# CATS-EUROC-Baro.net
KiCad netlist of a schematic drawn in Altium Designer
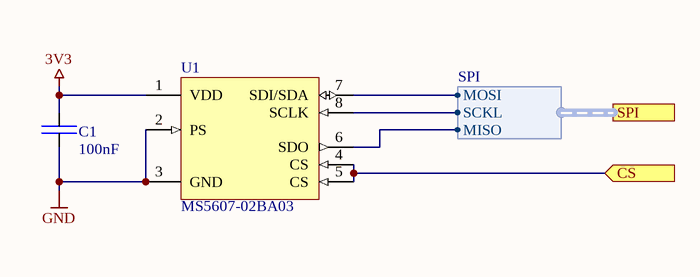
[diagram p0: CATS-EUROC-Baro.SchDoc]

(export (version "E")
  (design (tool "Eeschema 10.0.6"))
  (components
    (comp (ref "C1")
      (value "100nF")
      (footprint "SMD Keramikkondensator 0402")
      (description "SMD Ceramic Capacitor E6")
      (libsource (lib "CATS-EUROC") (part "E6 - 100nF"))
    )
    (comp (ref "U1")
      (value "MS5607-02BA03")
      (footprint "SMD IC BARO MS5607")
      (description "Barometric Pressure Sensor, with stainless\r\nsteel cap")
      (libsource (lib "Sensors") (part "MS5607-02BA03"))
    )
  )
  (nets
    (net (code "2") (name "/CS") (class "Default")
      (node (ref "U1") (pin "4") (pinfunction "CS_4") (pintype "input"))
      (node (ref "U1") (pin "5") (pinfunction "CS_5") (pintype "input"))
    )
    (net (code "3") (name "/MISO") (class "Default")
      (node (ref "U1") (pin "6") (pinfunction "SDO_6") (pintype "output"))
    )
    (net (code "4") (name "/MOSI") (class "Default")
      (node (ref "U1") (pin "7") (pinfunction "SDI/SDA_7") (pintype "bidirectional"))
    )
    (net (code "5") (name "/SCKL") (class "Default")
      (node (ref "U1") (pin "8") (pinfunction "SCLK_8") (pintype "input"))
    )
    (net (code "7") (name "3V3") (class "Default")
      (node (ref "C1") (pin "2") (pinfunction "2_2") (pintype "passive"))
      (node (ref "U1") (pin "1") (pinfunction "VDD_1") (pintype "passive"))
    )
    (net (code "8") (name "GND") (class "Default")
      (node (ref "C1") (pin "1") (pinfunction "1_1") (pintype "passive"))
      (node (ref "U1") (pin "2") (pinfunction "PS_2") (pintype "input"))
      (node (ref "U1") (pin "3") (pinfunction "GND_3") (pintype "passive"))
    )
  )
)
